# YOTSUBA_GNSS-receiver_ver_1_1.net
KiCad netlist of a schematic drawn in EAGLE
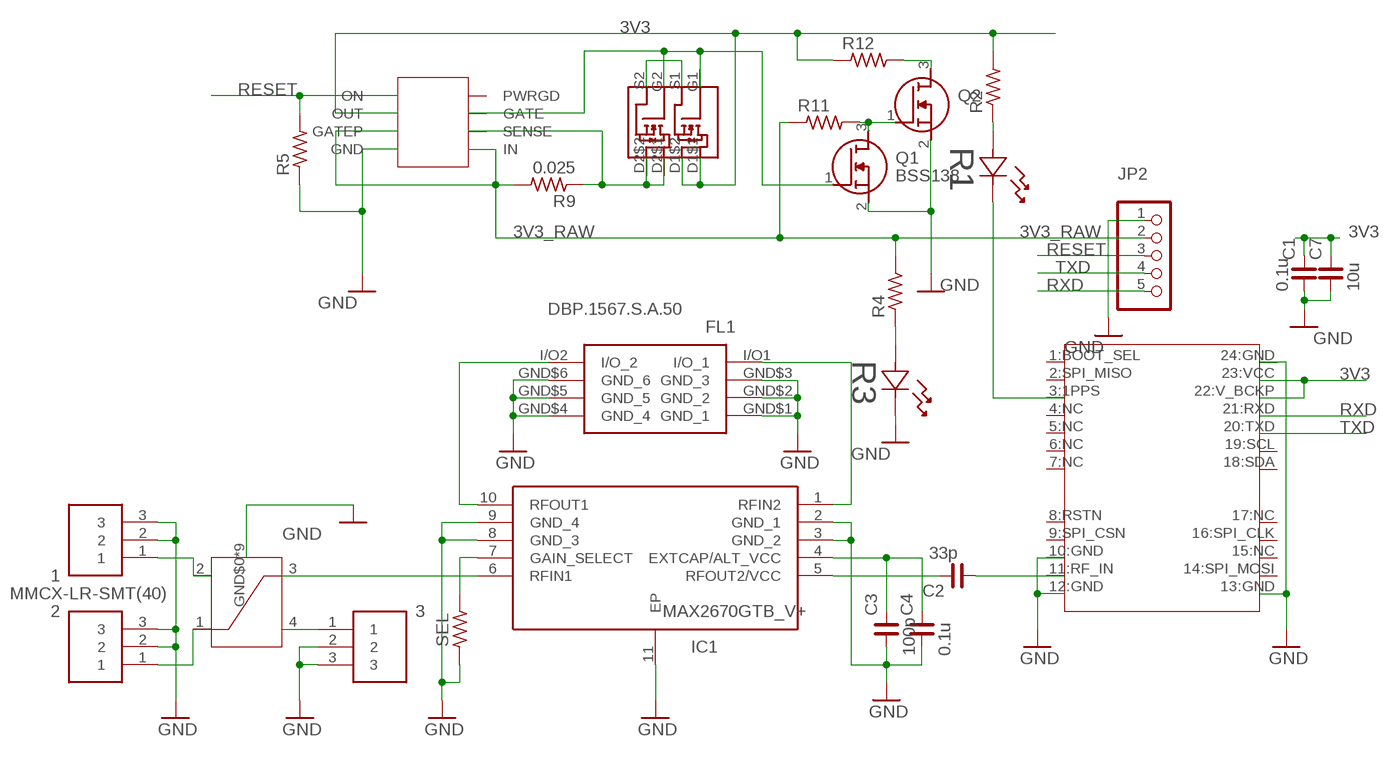
[diagram p0: schematic, sheet 1]

(export (version "E")
  (design (tool "Eeschema 10.0.6"))
  (components
    (comp (ref "1")
      (value "MMCX-LR-SMT(40)")
      (footprint "eagle-import:MMCX-LR-SMT(40)")
      (libsource (lib "eagle-import") (part "MMCX-LR-SMT(40)"))
    )
    (comp (ref "2")
      (value "MMCX-LR-SMT(40)")
      (footprint "eagle-import:MMCX-LR-SMT(40)")
      (libsource (lib "eagle-import") (part "MMCX-LR-SMT(40)"))
    )
    (comp (ref "3")
      (value "MMCX-LR-SMT(40)")
      (footprint "eagle-import:MMCX-LR-SMT(40)")
      (libsource (lib "eagle-import") (part "MMCX-LR-SMT(40)"))
    )
    (comp (ref "C1")
      (value "0.1u")
      (footprint "eagle-import:C0603")
      (libsource (lib "eagle-import") (part "C_0603"))
    )
    (comp (ref "C2")
      (value "33p")
      (footprint "eagle-import:C0603")
      (libsource (lib "eagle-import") (part "C_0603"))
    )
    (comp (ref "C3")
      (value "100p")
      (footprint "eagle-import:C0603")
      (libsource (lib "eagle-import") (part "C_0603"))
    )
    (comp (ref "C4")
      (value "0.1u")
      (footprint "eagle-import:C0603")
      (libsource (lib "eagle-import") (part "C_0603"))
    )
    (comp (ref "C7")
      (value "10u")
      (footprint "eagle-import:C0603")
      (libsource (lib "eagle-import") (part "C_0603"))
    )
    (comp (ref "FL1")
      (value "DBP.1567.S.A.50")
      (footprint "eagle-import:DBP1567SA50")
      (libsource (lib "eagle-import") (part "DBP.1567.S.A.50"))
    )
    (comp (ref "IC1")
      (value "MAX2670GTB_V+")
      (footprint "eagle-import:SON50P300X300X80-11N")
      (fields
        (field (name "MANUFACTURER_PART_NUMBER") "MAX2670GTB/V+")
        (field (name "MOUSER_PART_NUMBER") "700-MAX2670GTB/V+")
      )
      (libsource (lib "eagle-import") (part "MAX2670GTB_V+"))
    )
    (comp (ref "JP2")
      (value "PINHD-1X5")
      (footprint "eagle-import:1X05")
      (libsource (lib "eagle-import") (part "PINHD-1X5"))
    )
    (comp (ref "Q1")
      (value "BSS138")
      (footprint "eagle-import:SOT95P240X120-3N")
      (fields (field (name "MOUSER_PART_NUMBER") "512-BSS138"))
      (libsource (lib "eagle-import") (part "BSS138"))
    )
    (comp (ref "Q2")
      (value "BSS138")
      (footprint "eagle-import:SOT95P240X120-3N")
      (fields (field (name "MOUSER_PART_NUMBER") "512-BSS138"))
      (libsource (lib "eagle-import") (part "BSS138"))
    )
    (comp (ref "R1")
      (value "SML-E12P8WT86")
      (footprint "eagle-import:LED_SMLD12_ROM")
      (fields (field (name "COPYRIGHT") "Copyright (C) 2023 Ultra Librarian. All rights reserved."))
      (libsource (lib "eagle-import") (part "SML-E12P8WT86"))
    )
    (comp (ref "R2")
      (value "R_0603")
      (footprint "eagle-import:R0603")
      (libsource (lib "eagle-import") (part "R_0603"))
    )
    (comp (ref "R3")
      (value "SML-E12P8WT86")
      (footprint "eagle-import:LED_SMLD12_ROM")
      (fields (field (name "COPYRIGHT") "Copyright (C) 2023 Ultra Librarian. All rights reserved."))
      (libsource (lib "eagle-import") (part "SML-E12P8WT86"))
    )
    (comp (ref "R4")
      (value "R_0603")
      (footprint "eagle-import:R0603")
      (libsource (lib "eagle-import") (part "R_0603"))
    )
    (comp (ref "R5")
      (value "R_0603")
      (footprint "eagle-import:R0603")
      (libsource (lib "eagle-import") (part "R_0603"))
    )
    (comp (ref "R9")
      (value "0.025")
      (footprint "eagle-import:R0603")
      (libsource (lib "eagle-import") (part "R_0603"))
    )
    (comp (ref "R11")
      (value "R_0603")
      (footprint "eagle-import:R0603")
      (libsource (lib "eagle-import") (part "R_0603"))
    )
    (comp (ref "R12")
      (value "R_0603")
      (footprint "eagle-import:R0603")
      (libsource (lib "eagle-import") (part "R_0603"))
    )
    (comp (ref "SEL")
      (value "R_0603")
      (footprint "eagle-import:R0603")
      (libsource (lib "eagle-import") (part "R_0603"))
    )
    (comp (ref "U$1")
      (value "ORION_B16")
      (footprint "eagle-import:ORION_B16")
      (libsource (lib "eagle-import") (part "ORION_B16"))
    )
    (comp (ref "U$3")
      (value "HC125.A")
      (footprint "eagle-import:HC125.A")
      (libsource (lib "eagle-import") (part "HC125.A"))
    )
    (comp (ref "U$7")
      (value "DMG6898LSD")
      (footprint "eagle-import:SOIC127P600X150-8N")
      (libsource (lib "eagle-import") (part "DMG6898LSD"))
    )
    (comp (ref "U$8")
      (value "LTC4361")
      (footprint "eagle-import:SOP65P280X100-8N")
      (libsource (lib "eagle-import") (part "LTC4361"))
    )
  )
  (nets
    (net (code "1") (name "/3V3") (class "Default")
      (node (ref "C1") (pin "2") (pinfunction "2_2") (pintype "passive"))
      (node (ref "C7") (pin "2") (pinfunction "2_2") (pintype "passive"))
      (node (ref "R12") (pin "1") (pinfunction "1_1") (pintype "passive"))
      (node (ref "R2") (pin "2") (pinfunction "2_2") (pintype "passive"))
      (node (ref "U$1") (pin "22:V_BCKP") (pinfunction "22:V_BCKP_22:V_BCKP") (pintype "bidirectional"))
      (node (ref "U$1") (pin "23:VCC") (pinfunction "23:VCC_23:VCC") (pintype "bidirectional"))
      (node (ref "U$7") (pin "D1$1") (pinfunction "D1$1_D1$1") (pintype "bidirectional"))
      (node (ref "U$7") (pin "D1$2") (pinfunction "D1$2_D1$2") (pintype "bidirectional"))
      (node (ref "U$8") (pin "OUT") (pinfunction "OUT_OUT") (pintype "bidirectional"))
    )
    (net (code "2") (name "/3V3_RAW") (class "Default")
      (node (ref "JP2") (pin "2") (pinfunction "2_2") (pintype "passive"))
      (node (ref "R11") (pin "1") (pinfunction "1_1") (pintype "passive"))
      (node (ref "R4") (pin "2") (pinfunction "2_2") (pintype "passive"))
      (node (ref "R9") (pin "2") (pinfunction "2_2") (pintype "passive"))
      (node (ref "U$8") (pin "GATEP") (pinfunction "GATEP_GATEP") (pintype "bidirectional"))
      (node (ref "U$8") (pin "IN") (pinfunction "IN_IN") (pintype "bidirectional"))
    )
    (net (code "3") (name "/RESET") (class "Default")
      (node (ref "JP2") (pin "3") (pinfunction "3_3") (pintype "passive"))
      (node (ref "R5") (pin "2") (pinfunction "2_2") (pintype "passive"))
      (node (ref "U$8") (pin "ON") (pinfunction "ON_ON") (pintype "bidirectional"))
    )
    (net (code "4") (name "/RXD") (class "Default")
      (node (ref "JP2") (pin "5") (pinfunction "5_5") (pintype "passive"))
      (node (ref "U$1") (pin "21:RXD") (pinfunction "21:RXD_21:RXD") (pintype "bidirectional"))
    )
    (net (code "5") (name "/TXD") (class "Default")
      (node (ref "JP2") (pin "4") (pinfunction "4_4") (pintype "passive"))
      (node (ref "U$1") (pin "20:TXD") (pinfunction "20:TXD_20:TXD") (pintype "bidirectional"))
    )
    (net (code "6") (name "GND") (class "Default")
      (node (ref "1") (pin "2") (pinfunction "2_2") (pintype "bidirectional"))
      (node (ref "1") (pin "3") (pinfunction "3_3") (pintype "bidirectional"))
      (node (ref "2") (pin "2") (pinfunction "2_2") (pintype "bidirectional"))
      (node (ref "2") (pin "3") (pinfunction "3_3") (pintype "bidirectional"))
      (node (ref "3") (pin "2") (pinfunction "2_2") (pintype "bidirectional"))
      (node (ref "3") (pin "3") (pinfunction "3_3") (pintype "bidirectional"))
      (node (ref "C1") (pin "1") (pinfunction "1_1") (pintype "passive"))
      (node (ref "C3") (pin "1") (pinfunction "1_1") (pintype "passive"))
      (node (ref "C4") (pin "1") (pinfunction "1_1") (pintype "passive"))
      (node (ref "C7") (pin "1") (pinfunction "1_1") (pintype "passive"))
      (node (ref "FL1") (pin "GND$1") (pinfunction "GND_1_GND$1") (pintype "bidirectional"))
      (node (ref "FL1") (pin "GND$2") (pinfunction "GND_2_GND$2") (pintype "bidirectional"))
      (node (ref "FL1") (pin "GND$3") (pinfunction "GND_3_GND$3") (pintype "bidirectional"))
      (node (ref "FL1") (pin "GND$4") (pinfunction "GND_4_GND$4") (pintype "bidirectional"))
      (node (ref "FL1") (pin "GND$5") (pinfunction "GND_5_GND$5") (pintype "bidirectional"))
      (node (ref "FL1") (pin "GND$6") (pinfunction "GND_6_GND$6") (pintype "bidirectional"))
      (node (ref "IC1") (pin "11") (pinfunction "EP_11") (pintype "bidirectional"))
      (node (ref "IC1") (pin "2") (pinfunction "GND_1_2") (pintype "bidirectional"))
      (node (ref "IC1") (pin "3") (pinfunction "GND_2_3") (pintype "bidirectional"))
      (node (ref "IC1") (pin "8") (pinfunction "GND_3_8") (pintype "bidirectional"))
      (node (ref "IC1") (pin "9") (pinfunction "GND_4_9") (pintype "bidirectional"))
      (node (ref "JP2") (pin "1") (pinfunction "1_1") (pintype "passive"))
      (node (ref "Q1") (pin "2") (pinfunction "S_2") (pintype "bidirectional"))
      (node (ref "Q2") (pin "2") (pinfunction "S_2") (pintype "bidirectional"))
      (node (ref "R3") (pin "1") (pinfunction "1_1") (pintype "passive"))
      (node (ref "R5") (pin "1") (pinfunction "1_1") (pintype "passive"))
      (node (ref "SEL") (pin "1") (pinfunction "1_1") (pintype "passive"))
      (node (ref "U$1") (pin "10:GND") (pinfunction "10:GND_10:GND") (pintype "bidirectional"))
      (node (ref "U$1") (pin "12:GND") (pinfunction "12:GND_12:GND") (pintype "bidirectional"))
      (node (ref "U$1") (pin "13:GND") (pinfunction "13:GND_13:GND") (pintype "bidirectional"))
      (node (ref "U$1") (pin "24:GND") (pinfunction "24:GND_24:GND") (pintype "bidirectional"))
      (node (ref "U$3") (pin "GND$0") (pinfunction "GND_GND$0") (pintype "bidirectional"))
      (node (ref "U$3") (pin "GND$1") (pinfunction "GND_GND$1") (pintype "bidirectional"))
      (node (ref "U$3") (pin "GND$2") (pinfunction "GND_GND$2") (pintype "bidirectional"))
      (node (ref "U$3") (pin "GND$3") (pinfunction "GND_GND$3") (pintype "bidirectional"))
      (node (ref "U$3") (pin "GND$4") (pinfunction "GND_GND$4") (pintype "bidirectional"))
      (node (ref "U$3") (pin "GND$5") (pinfunction "GND_GND$5") (pintype "bidirectional"))
      (node (ref "U$3") (pin "GND$6") (pinfunction "GND_GND$6") (pintype "bidirectional"))
      (node (ref "U$3") (pin "GND$7") (pinfunction "GND_GND$7") (pintype "bidirectional"))
      (node (ref "U$3") (pin "GND$8") (pinfunction "GND_GND$8") (pintype "bidirectional"))
      (node (ref "U$8") (pin "GND") (pinfunction "GND_GND") (pintype "bidirectional"))
    )
    (net (code "7") (name "Net-(1-Pad1)") (class "Default")
      (node (ref "1") (pin "1") (pinfunction "1_1") (pintype "bidirectional"))
      (node (ref "U$3") (pin "2") (pinfunction "2_2") (pintype "bidirectional"))
    )
    (net (code "8") (name "Net-(2-Pad1)") (class "Default")
      (node (ref "2") (pin "1") (pinfunction "1_1") (pintype "bidirectional"))
      (node (ref "U$3") (pin "1") (pinfunction "1_1") (pintype "bidirectional"))
    )
    (net (code "9") (name "Net-(3-Pad1)") (class "Default")
      (node (ref "3") (pin "1") (pinfunction "1_1") (pintype "bidirectional"))
      (node (ref "U$3") (pin "4") (pinfunction "4_4") (pintype "bidirectional"))
    )
    (net (code "10") (name "Net-(C2-Pad1)") (class "Default")
      (node (ref "C2") (pin "1") (pinfunction "1_1") (pintype "passive"))
      (node (ref "U$1") (pin "11:RF_IN") (pinfunction "11:RF_IN_11:RF_IN") (pintype "bidirectional"))
    )
    (net (code "11") (name "Net-(FL1-I{slash}O_1)") (class "Default")
      (node (ref "FL1") (pin "I/O1") (pinfunction "I/O_1_I/O1") (pintype "bidirectional"))
      (node (ref "IC1") (pin "1") (pinfunction "RFIN2_1") (pintype "bidirectional"))
    )
    (net (code "12") (name "Net-(FL1-I{slash}O_2)") (class "Default")
      (node (ref "FL1") (pin "I/O2") (pinfunction "I/O_2_I/O2") (pintype "bidirectional"))
      (node (ref "IC1") (pin "10") (pinfunction "RFOUT1_10") (pintype "bidirectional"))
    )
    (net (code "13") (name "Net-(IC1-EXTCAP{slash}ALT_VCC)") (class "Default")
      (node (ref "C3") (pin "2") (pinfunction "2_2") (pintype "passive"))
      (node (ref "C4") (pin "2") (pinfunction "2_2") (pintype "passive"))
      (node (ref "IC1") (pin "4") (pinfunction "EXTCAP/ALT_VCC_4") (pintype "bidirectional"))
    )
    (net (code "14") (name "Net-(IC1-GAIN_SELECT)") (class "Default")
      (node (ref "IC1") (pin "7") (pinfunction "GAIN_SELECT_7") (pintype "bidirectional"))
      (node (ref "SEL") (pin "2") (pinfunction "2_2") (pintype "passive"))
    )
    (net (code "15") (name "Net-(IC1-RFIN1)") (class "Default")
      (node (ref "IC1") (pin "6") (pinfunction "RFIN1_6") (pintype "bidirectional"))
      (node (ref "U$3") (pin "3") (pinfunction "3_3") (pintype "bidirectional"))
    )
    (net (code "16") (name "Net-(IC1-RFOUT2{slash}VCC)") (class "Default")
      (node (ref "C2") (pin "2") (pinfunction "2_2") (pintype "passive"))
      (node (ref "IC1") (pin "5") (pinfunction "RFOUT2/VCC_5") (pintype "bidirectional"))
    )
    (net (code "17") (name "Net-(Q1-D)") (class "Default")
      (node (ref "Q1") (pin "3") (pinfunction "D_3") (pintype "bidirectional"))
      (node (ref "Q2") (pin "1") (pinfunction "G_1") (pintype "bidirectional"))
      (node (ref "R11") (pin "2") (pinfunction "2_2") (pintype "passive"))
    )
    (net (code "18") (name "Net-(Q1-G)") (class "Default")
      (node (ref "Q1") (pin "1") (pinfunction "G_1") (pintype "bidirectional"))
      (node (ref "U$7") (pin "G1") (pinfunction "G1_G1") (pintype "bidirectional"))
      (node (ref "U$7") (pin "G2") (pinfunction "G2_G2") (pintype "bidirectional"))
      (node (ref "U$8") (pin "GATE") (pinfunction "GATE_GATE") (pintype "bidirectional"))
    )
    (net (code "19") (name "Net-(Q2-D)") (class "Default")
      (node (ref "Q2") (pin "3") (pinfunction "D_3") (pintype "bidirectional"))
      (node (ref "R12") (pin "2") (pinfunction "2_2") (pintype "passive"))
    )
    (net (code "20") (name "Net-(R1-Pad1)") (class "Default")
      (node (ref "R1") (pin "1") (pinfunction "1_1") (pintype "passive"))
      (node (ref "U$1") (pin "3:1PPS") (pinfunction "3:1PPS_3:1PPS") (pintype "bidirectional"))
    )
    (net (code "21") (name "Net-(R1-Pad2)") (class "Default")
      (node (ref "R1") (pin "2") (pinfunction "2_2") (pintype "passive"))
      (node (ref "R2") (pin "1") (pinfunction "1_1") (pintype "passive"))
    )
    (net (code "22") (name "Net-(R3-Pad2)") (class "Default")
      (node (ref "R3") (pin "2") (pinfunction "2_2") (pintype "passive"))
      (node (ref "R4") (pin "1") (pinfunction "1_1") (pintype "passive"))
    )
    (net (code "23") (name "Net-(R9-Pad1)") (class "Default")
      (node (ref "R9") (pin "1") (pinfunction "1_1") (pintype "passive"))
      (node (ref "U$7") (pin "D2$1") (pinfunction "D2$1_D2$1") (pintype "bidirectional"))
      (node (ref "U$7") (pin "D2$2") (pinfunction "D2$2_D2$2") (pintype "bidirectional"))
      (node (ref "U$8") (pin "SENSE") (pinfunction "SENSE_SENSE") (pintype "bidirectional"))
    )
    (net (code "24") (name "Net-(U$7-PadS1)") (class "Default")
      (node (ref "U$7") (pin "S1") (pinfunction "S1_S1") (pintype "bidirectional"))
      (node (ref "U$7") (pin "S2") (pinfunction "S2_S2") (pintype "bidirectional"))
    )
    (net (code "25") (name "unconnected-(U$1-Pad1:BOOT_SEL)") (class "Default")
      (node (ref "U$1") (pin "1:BOOT_SEL") (pinfunction "1:BOOT_SEL_1:BOOT_SEL") (pintype "bidirectional"))
    )
    (net (code "26") (name "unconnected-(U$1-Pad2:SPI_MISO)") (class "Default")
      (node (ref "U$1") (pin "2:SPI_MISO") (pinfunction "2:SPI_MISO_2:SPI_MISO") (pintype "bidirectional"))
    )
    (net (code "27") (name "unconnected-(U$1-Pad4:NC)") (class "Default")
      (node (ref "U$1") (pin "4:NC") (pinfunction "4:NC_4:NC") (pintype "bidirectional"))
    )
    (net (code "28") (name "unconnected-(U$1-Pad5:NC)") (class "Default")
      (node (ref "U$1") (pin "5:NC") (pinfunction "5:NC_5:NC") (pintype "bidirectional"))
    )
    (net (code "29") (name "unconnected-(U$1-Pad6:NC)") (class "Default")
      (node (ref "U$1") (pin "6:NC") (pinfunction "6:NC_6:NC") (pintype "bidirectional"))
    )
    (net (code "30") (name "unconnected-(U$1-Pad7:NC)") (class "Default")
      (node (ref "U$1") (pin "7:NC") (pinfunction "7:NC_7:NC") (pintype "bidirectional"))
    )
    (net (code "31") (name "unconnected-(U$1-Pad8:RSTN)") (class "Default")
      (node (ref "U$1") (pin "8:RSTN") (pinfunction "8:RSTN_8:RSTN") (pintype "bidirectional"))
    )
    (net (code "32") (name "unconnected-(U$1-Pad9:SPI_CSN)") (class "Default")
      (node (ref "U$1") (pin "9:SPI_CSN") (pinfunction "9:SPI_CSN_9:SPI_CSN") (pintype "bidirectional"))
    )
    (net (code "33") (name "unconnected-(U$1-Pad14:SPI_MOSI)") (class "Default")
      (node (ref "U$1") (pin "14:SPI_MOSI") (pinfunction "14:SPI_MOSI_14:SPI_MOSI") (pintype "bidirectional"))
    )
    (net (code "34") (name "unconnected-(U$1-Pad15:NC)") (class "Default")
      (node (ref "U$1") (pin "15:NC") (pinfunction "15:NC_15:NC") (pintype "bidirectional"))
    )
    (net (code "35") (name "unconnected-(U$1-Pad16:SPI_CLK)") (class "Default")
      (node (ref "U$1") (pin "16:SPI_CLK") (pinfunction "16:SPI_CLK_16:SPI_CLK") (pintype "bidirectional"))
    )
    (net (code "36") (name "unconnected-(U$1-Pad17:NC)") (class "Default")
      (node (ref "U$1") (pin "17:NC") (pinfunction "17:NC_17:NC") (pintype "bidirectional"))
    )
    (net (code "37") (name "unconnected-(U$1-Pad18:SDA)") (class "Default")
      (node (ref "U$1") (pin "18:SDA") (pinfunction "18:SDA_18:SDA") (pintype "bidirectional"))
    )
    (net (code "38") (name "unconnected-(U$1-Pad19:SCL)") (class "Default")
      (node (ref "U$1") (pin "19:SCL") (pinfunction "19:SCL_19:SCL") (pintype "bidirectional"))
    )
    (net (code "39") (name "unconnected-(U$8-PadPWRGD)") (class "Default")
      (node (ref "U$8") (pin "PWRGD") (pinfunction "PWRGD_PWRGD") (pintype "bidirectional"))
    )
  )
)
